# SCH_vibration_array.net
KiCad netlist of a schematic drawn in Altium Designer
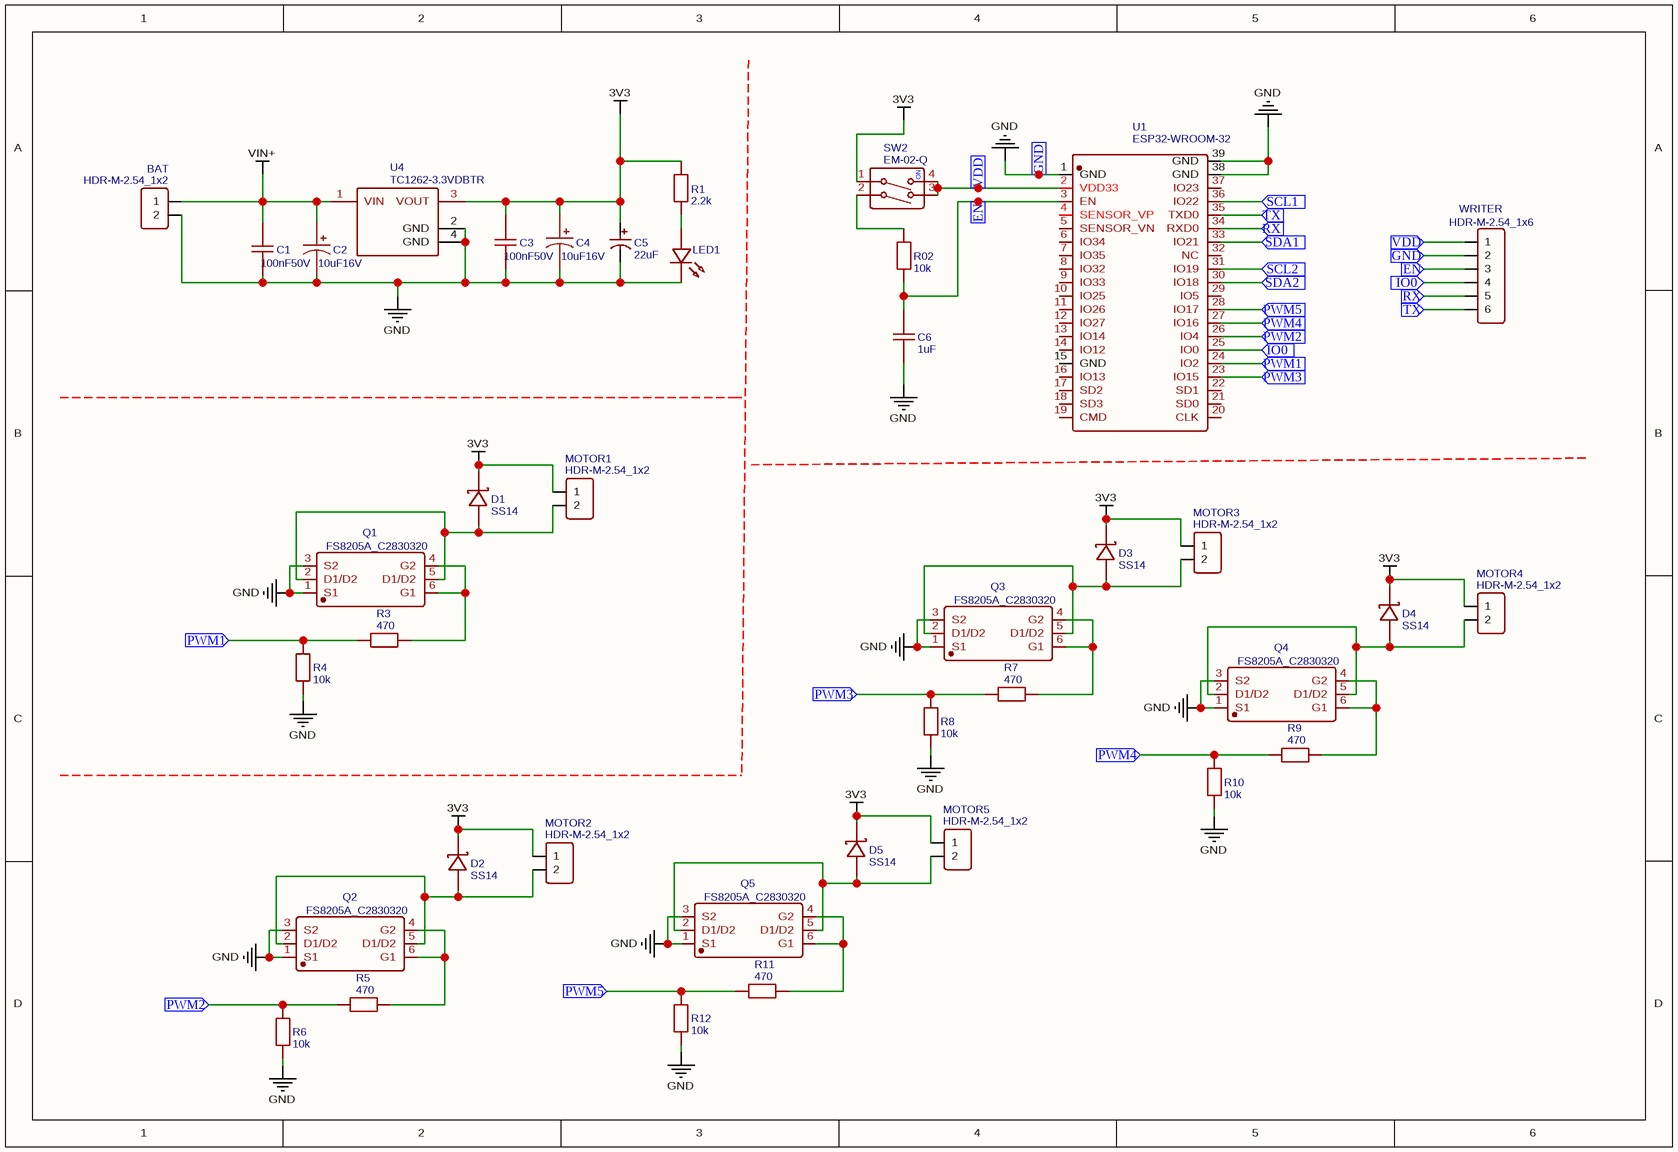
[diagram p0: SCH_vibration_array.schdoc]

(export (version "E")
  (design (tool "Eeschema 10.0.6"))
  (components
    (comp (ref "BAT")
      (value "HDR-M-2.54_1x2")
      (fields (field (name "BOM_SUPPLIER PART") "C124375") (field (name "CONTRIBUTOR") "LCEDA_Lib"))
      (libsource (lib "") (part "root_0_HDR-M-2.54_1x2__1"))
    )
    (comp (ref "C1")
      (value "100nF50V")
      (fields (field (name "CONTRIBUTOR") "LCEDA_Lib"))
      (libsource (lib "altium-import") (part "root_1_100nF50V_"))
    )
    (comp (ref "C2")
      (value "10uF16V")
      (fields (field (name "CONTRIBUTOR") "LCEDA_Lib"))
      (libsource (lib "altium-import") (part "root_3_10uF16V_"))
    )
    (comp (ref "C3")
      (value "100nF50V")
      (fields (field (name "CONTRIBUTOR") "LCEDA_Lib"))
      (libsource (lib "altium-import") (part "root_1_100nF50V_"))
    )
    (comp (ref "C4")
      (value "10uF16V")
      (fields (field (name "CONTRIBUTOR") "LCEDA_Lib"))
      (libsource (lib "altium-import") (part "root_3_10uF16V_"))
    )
    (comp (ref "C5")
      (value "22uF")
      (fields
        (field (name "BOM_MANUFACTURER PART") "22uF 50V 5*11")
        (field (name "BOM_SUPPLIER PART") "C43346")
      )
      (libsource (lib "altium-import") (part "root_3_22uF_"))
    )
    (comp (ref "C6")
      (value "1uF")
      (fields (field (name "CONTRIBUTOR") "LCEDA_Lib"))
      (libsource (lib "altium-import") (part "root_1_1uF_"))
    )
    (comp (ref "D1")
      (value "SS14")
      (fields (field (name "BOM_SUPPLIER PART") "C2480"))
      (libsource (lib "altium-import") (part "root_3_SS14_"))
    )
    (comp (ref "D2")
      (value "SS14")
      (fields (field (name "BOM_SUPPLIER PART") "C2480"))
      (libsource (lib "altium-import") (part "root_3_SS14_"))
    )
    (comp (ref "D3")
      (value "SS14")
      (fields (field (name "BOM_SUPPLIER PART") "C2480"))
      (libsource (lib "altium-import") (part "root_3_SS14_"))
    )
    (comp (ref "D4")
      (value "SS14")
      (fields (field (name "BOM_SUPPLIER PART") "C2480"))
      (libsource (lib "altium-import") (part "root_3_SS14_"))
    )
    (comp (ref "D5")
      (value "SS14")
      (fields (field (name "BOM_SUPPLIER PART") "C2480"))
      (libsource (lib "altium-import") (part "root_3_SS14_"))
    )
    (comp (ref "LED1")
      (value "LED-0603_R")
      (fields
        (field (name "BOM_MANUFACTURER PART") "19-217/R6C-AL1M2VY/3T")
        (field (name "BOM_SUPPLIER PART") "C72044")
        (field (name "CONTRIBUTOR") "LCEDA_01")
      )
      (libsource (lib "altium-import") (part "root_3_LED-0603_R_"))
    )
    (comp (ref "MOTOR1")
      (value "HDR-M-2.54_1x2")
      (fields (field (name "BOM_SUPPLIER PART") "C124375") (field (name "CONTRIBUTOR") "LCEDA_Lib"))
      (libsource (lib "altium-import") (part "root_0_HDR-M-2.54_1x2_"))
    )
    (comp (ref "MOTOR2")
      (value "HDR-M-2.54_1x2")
      (fields (field (name "BOM_SUPPLIER PART") "C124375") (field (name "CONTRIBUTOR") "LCEDA_Lib"))
      (libsource (lib "altium-import") (part "root_0_HDR-M-2.54_1x2_"))
    )
    (comp (ref "MOTOR3")
      (value "HDR-M-2.54_1x2")
      (fields (field (name "BOM_SUPPLIER PART") "C124375") (field (name "CONTRIBUTOR") "LCEDA_Lib"))
      (libsource (lib "altium-import") (part "root_0_HDR-M-2.54_1x2_"))
    )
    (comp (ref "MOTOR4")
      (value "HDR-M-2.54_1x2")
      (fields (field (name "BOM_SUPPLIER PART") "C124375") (field (name "CONTRIBUTOR") "LCEDA_Lib"))
      (libsource (lib "altium-import") (part "root_0_HDR-M-2.54_1x2_"))
    )
    (comp (ref "MOTOR5")
      (value "HDR-M-2.54_1x2")
      (fields (field (name "BOM_SUPPLIER PART") "C124375") (field (name "CONTRIBUTOR") "LCEDA_Lib"))
      (libsource (lib "altium-import") (part "root_0_HDR-M-2.54_1x2_"))
    )
    (comp (ref "Q1")
      (value "FS8205A_C2830320")
      (fields
        (field (name "BOM_SUPPLIER PART") "C2830320")
        (field (name "BOM_MANUFACTURER PART") "FS8205A")
        (field (name "CONTRIBUTOR") "LCSC")
      )
      (libsource (lib "altium-import") (part "root_2_FS8205A_C2830320_"))
    )
    (comp (ref "Q2")
      (value "FS8205A_C2830320")
      (fields
        (field (name "BOM_SUPPLIER PART") "C2830320")
        (field (name "BOM_MANUFACTURER PART") "FS8205A")
        (field (name "CONTRIBUTOR") "LCSC")
      )
      (libsource (lib "altium-import") (part "root_2_FS8205A_C2830320_"))
    )
    (comp (ref "Q3")
      (value "FS8205A_C2830320")
      (fields
        (field (name "BOM_SUPPLIER PART") "C2830320")
        (field (name "BOM_MANUFACTURER PART") "FS8205A")
        (field (name "CONTRIBUTOR") "LCSC")
      )
      (libsource (lib "altium-import") (part "root_2_FS8205A_C2830320_"))
    )
    (comp (ref "Q4")
      (value "FS8205A_C2830320")
      (fields
        (field (name "BOM_SUPPLIER PART") "C2830320")
        (field (name "BOM_MANUFACTURER PART") "FS8205A")
        (field (name "CONTRIBUTOR") "LCSC")
      )
      (libsource (lib "altium-import") (part "root_2_FS8205A_C2830320_"))
    )
    (comp (ref "Q5")
      (value "FS8205A_C2830320")
      (fields
        (field (name "BOM_SUPPLIER PART") "C2830320")
        (field (name "BOM_MANUFACTURER PART") "FS8205A")
        (field (name "CONTRIBUTOR") "LCSC")
      )
      (libsource (lib "altium-import") (part "root_2_FS8205A_C2830320_"))
    )
    (comp (ref "R1")
      (value "2.2k")
      (fields (field (name "CONTRIBUTOR") "LCEDA_Lib"))
      (libsource (lib "altium-import") (part "root_1_2.2k_"))
    )
    (comp (ref "R02")
      (value "10k")
      (fields (field (name "CONTRIBUTOR") "LCEDA_Lib"))
      (libsource (lib "altium-import") (part "root_1_10k_"))
    )
    (comp (ref "R3")
      (value "470")
      (fields (field (name "CONTRIBUTOR") "LCEDA_Lib"))
      (libsource (lib "altium-import") (part "root_0_470_"))
    )
    (comp (ref "R4")
      (value "10k")
      (fields (field (name "CONTRIBUTOR") "LCEDA_Lib"))
      (libsource (lib "altium-import") (part "root_1_10k_"))
    )
    (comp (ref "R5")
      (value "470")
      (fields (field (name "CONTRIBUTOR") "LCEDA_Lib"))
      (libsource (lib "altium-import") (part "root_0_470_"))
    )
    (comp (ref "R6")
      (value "10k")
      (fields (field (name "CONTRIBUTOR") "LCEDA_Lib"))
      (libsource (lib "altium-import") (part "root_1_10k_"))
    )
    (comp (ref "R7")
      (value "470")
      (fields (field (name "CONTRIBUTOR") "LCEDA_Lib"))
      (libsource (lib "altium-import") (part "root_0_470_"))
    )
    (comp (ref "R8")
      (value "10k")
      (fields (field (name "CONTRIBUTOR") "LCEDA_Lib"))
      (libsource (lib "altium-import") (part "root_1_10k_"))
    )
    (comp (ref "R9")
      (value "470")
      (fields (field (name "CONTRIBUTOR") "LCEDA_Lib"))
      (libsource (lib "altium-import") (part "root_0_470_"))
    )
    (comp (ref "R10")
      (value "10k")
      (fields (field (name "CONTRIBUTOR") "LCEDA_Lib"))
      (libsource (lib "altium-import") (part "root_1_10k_"))
    )
    (comp (ref "R11")
      (value "470")
      (fields (field (name "CONTRIBUTOR") "LCEDA_Lib"))
      (libsource (lib "altium-import") (part "root_0_470_"))
    )
    (comp (ref "R12")
      (value "10k")
      (fields (field (name "CONTRIBUTOR") "LCEDA_Lib"))
      (libsource (lib "altium-import") (part "root_1_10k_"))
    )
    (comp (ref "SW2")
      (value "EM-02-Q")
      (fields (field (name "BOM_SUPPLIER PART") "C501539") (field (name "CONTRIBUTOR") "LCSC"))
      (libsource (lib "altium-import") (part "root_3_EM-02-Q_"))
    )
    (comp (ref "U1")
      (value "ESP32-WROOM-32")
      (fields (field (name "BOM_SUPPLIER PART") "C503587") (field (name "CONTRIBUTOR") "LCSC"))
      (libsource (lib "altium-import") (part "root_0_ESP32-WROOM-32_"))
    )
    (comp (ref "U4")
      (value "TC1262-3.3VDBTR")
      (fields (field (name "BOM_SUPPLIER PART") "C52507") (field (name "CONTRIBUTOR") "LCSC"))
      (libsource (lib "altium-import") (part "root_0_TC1262-3.3VDBTR_"))
    )
    (comp (ref "WRITER")
      (value "HDR-M-2.54_1x6")
      (fields (field (name "BOM_SUPPLIER PART") "C190819") (field (name "CONTRIBUTOR") "LCEDA_Lib"))
      (libsource (lib "altium-import") (part "root_0_HDR-M-2.54_1x6_"))
    )
  )
  (nets
    (net (code "1") (name "/EN") (class "Default")
      (node (ref "C6") (pin "2") (pinfunction "2_2") (pintype "passive"))
      (node (ref "R02") (pin "1") (pinfunction "1_1") (pintype "passive"))
      (node (ref "U1") (pin "3") (pinfunction "EN_3") (pintype "passive"))
      (node (ref "WRITER") (pin "3") (pinfunction "3_3") (pintype "passive"))
    )
    (net (code "2") (name "/IO0") (class "Default")
      (node (ref "U1") (pin "25") (pinfunction "IO0_25") (pintype "passive"))
      (node (ref "WRITER") (pin "4") (pinfunction "4_4") (pintype "passive"))
    )
    (net (code "3") (name "/PWM1") (class "Default")
      (node (ref "R3") (pin "1") (pinfunction "1_1") (pintype "passive"))
      (node (ref "R4") (pin "2") (pinfunction "2_2") (pintype "passive"))
      (node (ref "U1") (pin "24") (pinfunction "IO2_24") (pintype "passive"))
    )
    (net (code "4") (name "/PWM2") (class "Default")
      (node (ref "R5") (pin "1") (pinfunction "1_1") (pintype "passive"))
      (node (ref "R6") (pin "2") (pinfunction "2_2") (pintype "passive"))
      (node (ref "U1") (pin "26") (pinfunction "IO4_26") (pintype "passive"))
    )
    (net (code "5") (name "/PWM3") (class "Default")
      (node (ref "R7") (pin "1") (pinfunction "1_1") (pintype "passive"))
      (node (ref "R8") (pin "2") (pinfunction "2_2") (pintype "passive"))
      (node (ref "U1") (pin "23") (pinfunction "IO15_23") (pintype "passive"))
    )
    (net (code "6") (name "/PWM4") (class "Default")
      (node (ref "R10") (pin "2") (pinfunction "2_2") (pintype "passive"))
      (node (ref "R9") (pin "1") (pinfunction "1_1") (pintype "passive"))
      (node (ref "U1") (pin "27") (pinfunction "IO16_27") (pintype "passive"))
    )
    (net (code "7") (name "/PWM5") (class "Default")
      (node (ref "R11") (pin "1") (pinfunction "1_1") (pintype "passive"))
      (node (ref "R12") (pin "2") (pinfunction "2_2") (pintype "passive"))
      (node (ref "U1") (pin "28") (pinfunction "IO17_28") (pintype "passive"))
    )
    (net (code "8") (name "/RX") (class "Default")
      (node (ref "U1") (pin "34") (pinfunction "RXD0_34") (pintype "passive"))
      (node (ref "WRITER") (pin "5") (pinfunction "5_5") (pintype "passive"))
    )
    (net (code "9") (name "/SCL1") (class "Default")
      (node (ref "U1") (pin "36") (pinfunction "IO22_36") (pintype "passive"))
    )
    (net (code "10") (name "/SCL2") (class "Default")
      (node (ref "U1") (pin "31") (pinfunction "IO19_31") (pintype "passive"))
    )
    (net (code "11") (name "/SDA1") (class "Default")
      (node (ref "U1") (pin "33") (pinfunction "IO21_33") (pintype "passive"))
    )
    (net (code "12") (name "/SDA2") (class "Default")
      (node (ref "U1") (pin "30") (pinfunction "IO18_30") (pintype "passive"))
    )
    (net (code "13") (name "/TX") (class "Default")
      (node (ref "U1") (pin "35") (pinfunction "TXD0_35") (pintype "passive"))
      (node (ref "WRITER") (pin "6") (pinfunction "6_6") (pintype "passive"))
    )
    (net (code "14") (name "/VDD") (class "Default")
      (node (ref "SW2") (pin "3") (pinfunction "3_3") (pintype "passive"))
      (node (ref "SW2") (pin "4") (pinfunction "4_4") (pintype "passive"))
      (node (ref "U1") (pin "2") (pinfunction "VDD33_2") (pintype "passive"))
      (node (ref "WRITER") (pin "1") (pinfunction "1_1") (pintype "passive"))
    )
    (net (code "15") (name "3V3") (class "Default")
      (node (ref "C3") (pin "2") (pinfunction "2_2") (pintype "passive"))
      (node (ref "C4") (pin "1") (pinfunction "1_1") (pintype "passive"))
      (node (ref "C5") (pin "1") (pinfunction "1_1") (pintype "passive"))
      (node (ref "D1") (pin "1") (pinfunction "K_1") (pintype "passive"))
      (node (ref "D2") (pin "1") (pinfunction "K_1") (pintype "passive"))
      (node (ref "D3") (pin "1") (pinfunction "K_1") (pintype "passive"))
      (node (ref "D4") (pin "1") (pinfunction "K_1") (pintype "passive"))
      (node (ref "D5") (pin "1") (pinfunction "K_1") (pintype "passive"))
      (node (ref "MOTOR1") (pin "1") (pinfunction "1_1") (pintype "passive"))
      (node (ref "MOTOR2") (pin "1") (pinfunction "1_1") (pintype "passive"))
      (node (ref "MOTOR3") (pin "1") (pinfunction "1_1") (pintype "passive"))
      (node (ref "MOTOR4") (pin "1") (pinfunction "1_1") (pintype "passive"))
      (node (ref "MOTOR5") (pin "1") (pinfunction "1_1") (pintype "passive"))
      (node (ref "R1") (pin "2") (pinfunction "2_2") (pintype "passive"))
      (node (ref "SW2") (pin "1") (pinfunction "1_1") (pintype "passive"))
      (node (ref "U4") (pin "3") (pinfunction "VOUT_3") (pintype "passive"))
    )
    (net (code "16") (name "GND") (class "Default")
      (node (ref "BAT") (pin "2") (pinfunction "2_2") (pintype "passive"))
      (node (ref "C1") (pin "1") (pinfunction "1_1") (pintype "passive"))
      (node (ref "C2") (pin "2") (pinfunction "2_2") (pintype "passive"))
      (node (ref "C3") (pin "1") (pinfunction "1_1") (pintype "passive"))
      (node (ref "C4") (pin "2") (pinfunction "2_2") (pintype "passive"))
      (node (ref "C5") (pin "2") (pinfunction "2_2") (pintype "passive"))
      (node (ref "C6") (pin "1") (pinfunction "1_1") (pintype "passive"))
      (node (ref "LED1") (pin "2") (pinfunction "2_2") (pintype "passive"))
      (node (ref "Q1") (pin "1") (pinfunction "S1_1") (pintype "passive"))
      (node (ref "Q1") (pin "3") (pinfunction "S2_3") (pintype "passive"))
      (node (ref "Q2") (pin "1") (pinfunction "S1_1") (pintype "passive"))
      (node (ref "Q2") (pin "3") (pinfunction "S2_3") (pintype "passive"))
      (node (ref "Q3") (pin "1") (pinfunction "S1_1") (pintype "passive"))
      (node (ref "Q3") (pin "3") (pinfunction "S2_3") (pintype "passive"))
      (node (ref "Q4") (pin "1") (pinfunction "S1_1") (pintype "passive"))
      (node (ref "Q4") (pin "3") (pinfunction "S2_3") (pintype "passive"))
      (node (ref "Q5") (pin "1") (pinfunction "S1_1") (pintype "passive"))
      (node (ref "Q5") (pin "3") (pinfunction "S2_3") (pintype "passive"))
      (node (ref "R10") (pin "1") (pinfunction "1_1") (pintype "passive"))
      (node (ref "R12") (pin "1") (pinfunction "1_1") (pintype "passive"))
      (node (ref "R4") (pin "1") (pinfunction "1_1") (pintype "passive"))
      (node (ref "R6") (pin "1") (pinfunction "1_1") (pintype "passive"))
      (node (ref "R8") (pin "1") (pinfunction "1_1") (pintype "passive"))
      (node (ref "U1") (pin "1") (pinfunction "GND_1") (pintype "passive"))
      (node (ref "U1") (pin "38") (pinfunction "GND_38") (pintype "passive"))
      (node (ref "U1") (pin "39") (pinfunction "GND_39") (pintype "passive"))
      (node (ref "U4") (pin "2") (pinfunction "GND_2") (pintype "passive"))
      (node (ref "U4") (pin "4") (pinfunction "GND_4") (pintype "passive"))
      (node (ref "WRITER") (pin "2") (pinfunction "2_2") (pintype "passive"))
    )
    (net (code "17") (name "Net-(D1-A)") (class "Default")
      (node (ref "D1") (pin "2") (pinfunction "A_2") (pintype "passive"))
      (node (ref "MOTOR1") (pin "2") (pinfunction "2_2") (pintype "passive"))
      (node (ref "Q1") (pin "2") (pinfunction "D1/D2_2") (pintype "passive"))
      (node (ref "Q1") (pin "5") (pinfunction "D1/D2_5") (pintype "passive"))
    )
    (net (code "18") (name "Net-(D2-A)") (class "Default")
      (node (ref "D2") (pin "2") (pinfunction "A_2") (pintype "passive"))
      (node (ref "MOTOR2") (pin "2") (pinfunction "2_2") (pintype "passive"))
      (node (ref "Q2") (pin "2") (pinfunction "D1/D2_2") (pintype "passive"))
      (node (ref "Q2") (pin "5") (pinfunction "D1/D2_5") (pintype "passive"))
    )
    (net (code "19") (name "Net-(D3-A)") (class "Default")
      (node (ref "D3") (pin "2") (pinfunction "A_2") (pintype "passive"))
      (node (ref "MOTOR3") (pin "2") (pinfunction "2_2") (pintype "passive"))
      (node (ref "Q3") (pin "2") (pinfunction "D1/D2_2") (pintype "passive"))
      (node (ref "Q3") (pin "5") (pinfunction "D1/D2_5") (pintype "passive"))
    )
    (net (code "20") (name "Net-(D4-A)") (class "Default")
      (node (ref "D4") (pin "2") (pinfunction "A_2") (pintype "passive"))
      (node (ref "MOTOR4") (pin "2") (pinfunction "2_2") (pintype "passive"))
      (node (ref "Q4") (pin "2") (pinfunction "D1/D2_2") (pintype "passive"))
      (node (ref "Q4") (pin "5") (pinfunction "D1/D2_5") (pintype "passive"))
    )
    (net (code "21") (name "Net-(D5-A)") (class "Default")
      (node (ref "D5") (pin "2") (pinfunction "A_2") (pintype "passive"))
      (node (ref "MOTOR5") (pin "2") (pinfunction "2_2") (pintype "passive"))
      (node (ref "Q5") (pin "2") (pinfunction "D1/D2_2") (pintype "passive"))
      (node (ref "Q5") (pin "5") (pinfunction "D1/D2_5") (pintype "passive"))
    )
    (net (code "22") (name "Net-(LED1-Pad1)") (class "Default")
      (node (ref "LED1") (pin "1") (pinfunction "1_1") (pintype "passive"))
      (node (ref "R1") (pin "1") (pinfunction "1_1") (pintype "passive"))
    )
    (net (code "23") (name "Net-(Q1-G1)") (class "Default")
      (node (ref "Q1") (pin "4") (pinfunction "G2_4") (pintype "passive"))
      (node (ref "Q1") (pin "6") (pinfunction "G1_6") (pintype "passive"))
      (node (ref "R3") (pin "2") (pinfunction "2_2") (pintype "passive"))
    )
    (net (code "24") (name "Net-(Q2-G1)") (class "Default")
      (node (ref "Q2") (pin "4") (pinfunction "G2_4") (pintype "passive"))
      (node (ref "Q2") (pin "6") (pinfunction "G1_6") (pintype "passive"))
      (node (ref "R5") (pin "2") (pinfunction "2_2") (pintype "passive"))
    )
    (net (code "25") (name "Net-(Q3-G1)") (class "Default")
      (node (ref "Q3") (pin "4") (pinfunction "G2_4") (pintype "passive"))
      (node (ref "Q3") (pin "6") (pinfunction "G1_6") (pintype "passive"))
      (node (ref "R7") (pin "2") (pinfunction "2_2") (pintype "passive"))
    )
    (net (code "26") (name "Net-(Q4-G1)") (class "Default")
      (node (ref "Q4") (pin "4") (pinfunction "G2_4") (pintype "passive"))
      (node (ref "Q4") (pin "6") (pinfunction "G1_6") (pintype "passive"))
      (node (ref "R9") (pin "2") (pinfunction "2_2") (pintype "passive"))
    )
    (net (code "27") (name "Net-(Q5-G1)") (class "Default")
      (node (ref "Q5") (pin "4") (pinfunction "G2_4") (pintype "passive"))
      (node (ref "Q5") (pin "6") (pinfunction "G1_6") (pintype "passive"))
      (node (ref "R11") (pin "2") (pinfunction "2_2") (pintype "passive"))
    )
    (net (code "28") (name "Net-(R02-Pad2)") (class "Default")
      (node (ref "R02") (pin "2") (pinfunction "2_2") (pintype "passive"))
      (node (ref "SW2") (pin "2") (pinfunction "2_2") (pintype "passive"))
    )
    (net (code "29") (name "VIN+") (class "Default")
      (node (ref "BAT") (pin "1") (pinfunction "1_1") (pintype "passive"))
      (node (ref "C1") (pin "2") (pinfunction "2_2") (pintype "passive"))
      (node (ref "C2") (pin "1") (pinfunction "1_1") (pintype "passive"))
      (node (ref "U4") (pin "1") (pinfunction "VIN_1") (pintype "passive"))
    )
    (net (code "30") (name "unconnected-(U1-CLK-Pad20)") (class "Default")
      (node (ref "U1") (pin "20") (pinfunction "CLK_20") (pintype "passive"))
    )
    (net (code "31") (name "unconnected-(U1-CMD-Pad19)") (class "Default")
      (node (ref "U1") (pin "19") (pinfunction "CMD_19") (pintype "passive"))
    )
    (net (code "32") (name "unconnected-(U1-GND-Pad15)") (class "Default")
      (node (ref "U1") (pin "15") (pinfunction "GND_15") (pintype "passive"))
    )
    (net (code "33") (name "unconnected-(U1-IO5-Pad29)") (class "Default")
      (node (ref "U1") (pin "29") (pinfunction "IO5_29") (pintype "passive"))
    )
    (net (code "34") (name "unconnected-(U1-IO12-Pad14)") (class "Default")
      (node (ref "U1") (pin "14") (pinfunction "IO12_14") (pintype "passive"))
    )
    (net (code "35") (name "unconnected-(U1-IO13-Pad16)") (class "Default")
      (node (ref "U1") (pin "16") (pinfunction "IO13_16") (pintype "passive"))
    )
    (net (code "36") (name "unconnected-(U1-IO14-Pad13)") (class "Default")
      (node (ref "U1") (pin "13") (pinfunction "IO14_13") (pintype "passive"))
    )
    (net (code "37") (name "unconnected-(U1-IO23-Pad37)") (class "Default")
      (node (ref "U1") (pin "37") (pinfunction "IO23_37") (pintype "passive"))
    )
    (net (code "38") (name "unconnected-(U1-IO25-Pad10)") (class "Default")
      (node (ref "U1") (pin "10") (pinfunction "IO25_10") (pintype "passive"))
    )
    (net (code "39") (name "unconnected-(U1-IO26-Pad11)") (class "Default")
      (node (ref "U1") (pin "11") (pinfunction "IO26_11") (pintype "passive"))
    )
    (net (code "40") (name "unconnected-(U1-IO27-Pad12)") (class "Default")
      (node (ref "U1") (pin "12") (pinfunction "IO27_12") (pintype "passive"))
    )
    (net (code "41") (name "unconnected-(U1-IO32-Pad8)") (class "Default")
      (node (ref "U1") (pin "8") (pinfunction "IO32_8") (pintype "passive"))
    )
    (net (code "42") (name "unconnected-(U1-IO33-Pad9)") (class "Default")
      (node (ref "U1") (pin "9") (pinfunction "IO33_9") (pintype "passive"))
    )
    (net (code "43") (name "unconnected-(U1-IO34-Pad6)") (class "Default")
      (node (ref "U1") (pin "6") (pinfunction "IO34_6") (pintype "passive"))
    )
    (net (code "44") (name "unconnected-(U1-IO35-Pad7)") (class "Default")
      (node (ref "U1") (pin "7") (pinfunction "IO35_7") (pintype "passive"))
    )
    (net (code "45") (name "unconnected-(U1-NC-Pad32)") (class "Default")
      (node (ref "U1") (pin "32") (pinfunction "NC_32") (pintype "passive"))
    )
    (net (code "46") (name "unconnected-(U1-SD0-Pad21)") (class "Default")
      (node (ref "U1") (pin "21") (pinfunction "SD0_21") (pintype "passive"))
    )
    (net (code "47") (name "unconnected-(U1-SD1-Pad22)") (class "Default")
      (node (ref "U1") (pin "22") (pinfunction "SD1_22") (pintype "passive"))
    )
    (net (code "48") (name "unconnected-(U1-SD2-Pad17)") (class "Default")
      (node (ref "U1") (pin "17") (pinfunction "SD2_17") (pintype "passive"))
    )
    (net (code "49") (name "unconnected-(U1-SD3-Pad18)") (class "Default")
      (node (ref "U1") (pin "18") (pinfunction "SD3_18") (pintype "passive"))
    )
    (net (code "50") (name "unconnected-(U1-SENSOR_VN-Pad5)") (class "Default")
      (node (ref "U1") (pin "5") (pinfunction "SENSOR_VN_5") (pintype "passive"))
    )
    (net (code "51") (name "unconnected-(U1-SENSOR_VP-Pad4)") (class "Default")
      (node (ref "U1") (pin "4") (pinfunction "SENSOR_VP_4") (pintype "passive"))
    )
  )
)
